# 4017-7Segment.net
KiCad netlist of a schematic drawn in EAGLE
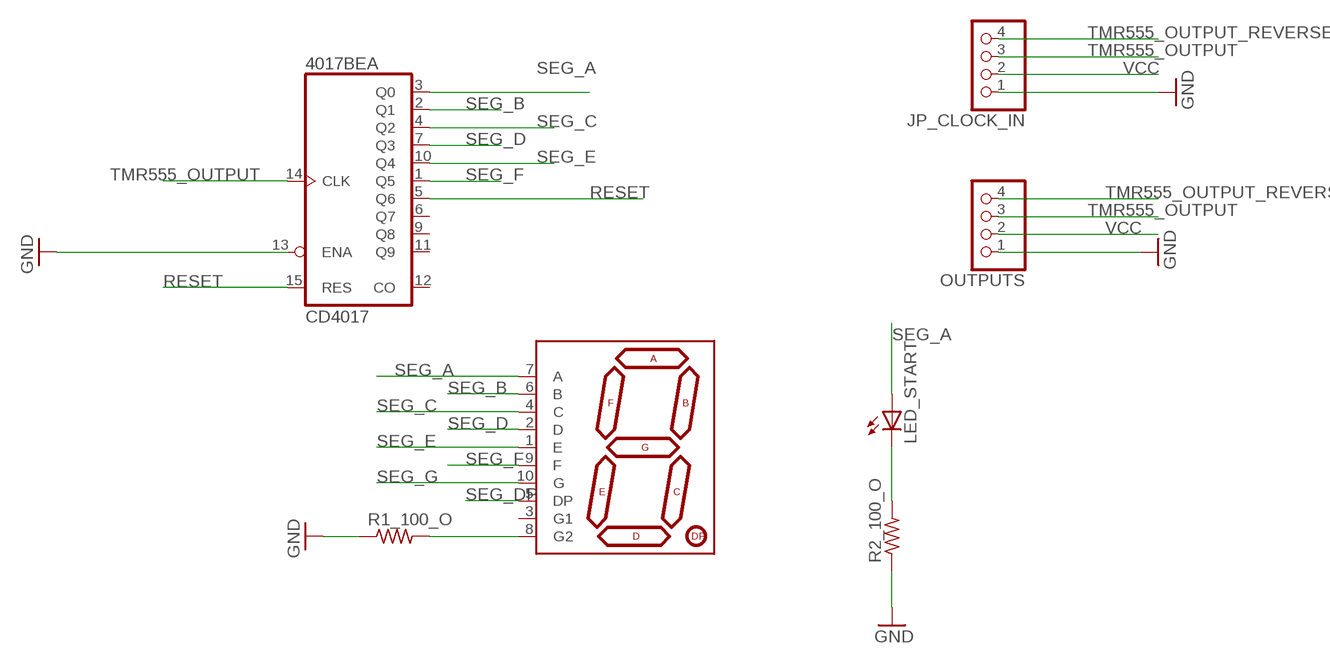
[diagram p0: schematic, sheet 1]

(export (version "E")
  (design (tool "Eeschema 10.0.6"))
  (components
    (comp (ref "4017BE")
      (value "CD4017")
      (footprint "eagle-import:DIL16")
      (libsource (lib "eagle-import") (part "CD4017"))
    )
    (comp (ref "JP_CLOCK_IN")
      (value "PINHD-1X4")
      (footprint "eagle-import:1X04")
      (libsource (lib "eagle-import") (part "PINHD-1X4"))
    )
    (comp (ref "LED_START")
      (value "LEDSMT1206")
      (footprint "eagle-import:1206")
      (libsource (lib "eagle-import") (part "LEDSMT1206"))
    )
    (comp (ref "OUTPUTS")
      (value "PINHD-1X4")
      (footprint "eagle-import:1X04")
      (libsource (lib "eagle-import") (part "PINHD-1X4"))
    )
    (comp (ref "R1_100_O")
      (value "R-US_R1206")
      (footprint "eagle-import:R1206")
      (libsource (lib "eagle-import") (part "R-US_R1206"))
    )
    (comp (ref "R2_100_O")
      (value "R-US_R1206")
      (footprint "eagle-import:R1206")
      (libsource (lib "eagle-import") (part "R-US_R1206"))
    )
    (comp (ref "U$1")
      (value "7-SEGMENT-DISPLAYPTH")
      (footprint "eagle-import:7-SEGMENT-DISPLAY")
      (libsource (lib "eagle-import") (part "7-SEGMENT-DISPLAYPTH"))
    )
  )
  (nets
    (net (code "1") (name "/RESET") (class "Default")
      (node (ref "4017BE") (pin "15") (pinfunction "RES_15") (pintype "input"))
      (node (ref "4017BE") (pin "5") (pinfunction "Q6_5") (pintype "output"))
    )
    (net (code "2") (name "/SEG_A") (class "Default")
      (node (ref "4017BE") (pin "3") (pinfunction "Q0_3") (pintype "output"))
      (node (ref "LED_START") (pin "A") (pinfunction "A_A") (pintype "passive"))
      (node (ref "U$1") (pin "7") (pinfunction "A_7") (pintype "bidirectional"))
    )
    (net (code "3") (name "/SEG_B") (class "Default")
      (node (ref "4017BE") (pin "2") (pinfunction "Q1_2") (pintype "output"))
      (node (ref "U$1") (pin "6") (pinfunction "B_6") (pintype "bidirectional"))
    )
    (net (code "4") (name "/SEG_C") (class "Default")
      (node (ref "4017BE") (pin "4") (pinfunction "Q2_4") (pintype "output"))
      (node (ref "U$1") (pin "4") (pinfunction "C_4") (pintype "bidirectional"))
    )
    (net (code "5") (name "/SEG_D") (class "Default")
      (node (ref "4017BE") (pin "7") (pinfunction "Q3_7") (pintype "output"))
      (node (ref "U$1") (pin "2") (pinfunction "D_2") (pintype "bidirectional"))
    )
    (net (code "6") (name "/SEG_DP") (class "Default")
      (node (ref "U$1") (pin "5") (pinfunction "DP_5") (pintype "bidirectional"))
    )
    (net (code "7") (name "/SEG_E") (class "Default")
      (node (ref "4017BE") (pin "10") (pinfunction "Q4_10") (pintype "output"))
      (node (ref "U$1") (pin "1") (pinfunction "E_1") (pintype "bidirectional"))
    )
    (net (code "8") (name "/SEG_F") (class "Default")
      (node (ref "4017BE") (pin "1") (pinfunction "Q5_1") (pintype "output"))
      (node (ref "U$1") (pin "9") (pinfunction "F_9") (pintype "bidirectional"))
    )
    (net (code "9") (name "/SEG_G") (class "Default")
      (node (ref "U$1") (pin "10") (pinfunction "G_10") (pintype "bidirectional"))
    )
    (net (code "10") (name "/TMR555_OUTPUT") (class "Default")
      (node (ref "4017BE") (pin "14") (pinfunction "CLK_14") (pintype "input"))
      (node (ref "JP_CLOCK_IN") (pin "3") (pinfunction "3_3") (pintype "passive"))
      (node (ref "OUTPUTS") (pin "3") (pinfunction "3_3") (pintype "passive"))
    )
    (net (code "11") (name "/TMR555_OUTPUT_REVERSE") (class "Default")
      (node (ref "JP_CLOCK_IN") (pin "4") (pinfunction "4_4") (pintype "passive"))
      (node (ref "OUTPUTS") (pin "4") (pinfunction "4_4") (pintype "passive"))
    )
    (net (code "12") (name "/VCC") (class "Default")
      (node (ref "JP_CLOCK_IN") (pin "2") (pinfunction "2_2") (pintype "passive"))
      (node (ref "OUTPUTS") (pin "2") (pinfunction "2_2") (pintype "passive"))
    )
    (net (code "13") (name "GND") (class "Default")
      (node (ref "4017BE") (pin "13") (pinfunction "ENA_13") (pintype "input"))
      (node (ref "JP_CLOCK_IN") (pin "1") (pinfunction "1_1") (pintype "passive"))
      (node (ref "OUTPUTS") (pin "1") (pinfunction "1_1") (pintype "passive"))
      (node (ref "R1_100_O") (pin "1") (pinfunction "1_1") (pintype "passive"))
      (node (ref "R2_100_O") (pin "1") (pinfunction "1_1") (pintype "passive"))
    )
    (net (code "14") (name "Net-(LED_START-PadC)") (class "Default")
      (node (ref "LED_START") (pin "C") (pinfunction "C_C") (pintype "passive"))
      (node (ref "R2_100_O") (pin "2") (pinfunction "2_2") (pintype "passive"))
    )
    (net (code "15") (name "Net-(U$1-G2)") (class "Default")
      (node (ref "R1_100_O") (pin "2") (pinfunction "2_2") (pintype "passive"))
      (node (ref "U$1") (pin "8") (pinfunction "G2_8") (pintype "bidirectional"))
    )
    (net (code "16") (name "unconnected-(4017BEA-CO-Pad12)") (class "Default")
      (node (ref "4017BE") (pin "12") (pinfunction "CO_12") (pintype "output"))
    )
    (net (code "17") (name "unconnected-(4017BEA-Q7-Pad6)") (class "Default")
      (node (ref "4017BE") (pin "6") (pinfunction "Q7_6") (pintype "output"))
    )
    (net (code "18") (name "unconnected-(4017BEA-Q8-Pad9)") (class "Default")
      (node (ref "4017BE") (pin "9") (pinfunction "Q8_9") (pintype "output"))
    )
    (net (code "19") (name "unconnected-(4017BEA-Q9-Pad11)") (class "Default")
      (node (ref "4017BE") (pin "11") (pinfunction "Q9_11") (pintype "output"))
    )
    (net (code "20") (name "unconnected-(U$1-G1-Pad3)") (class "Default")
      (node (ref "U$1") (pin "3") (pinfunction "G1_3") (pintype "bidirectional"))
    )
  )
)
